# HDMI_To_MIPI_PHY.net
KiCad netlist of a schematic drawn in Altium Designer
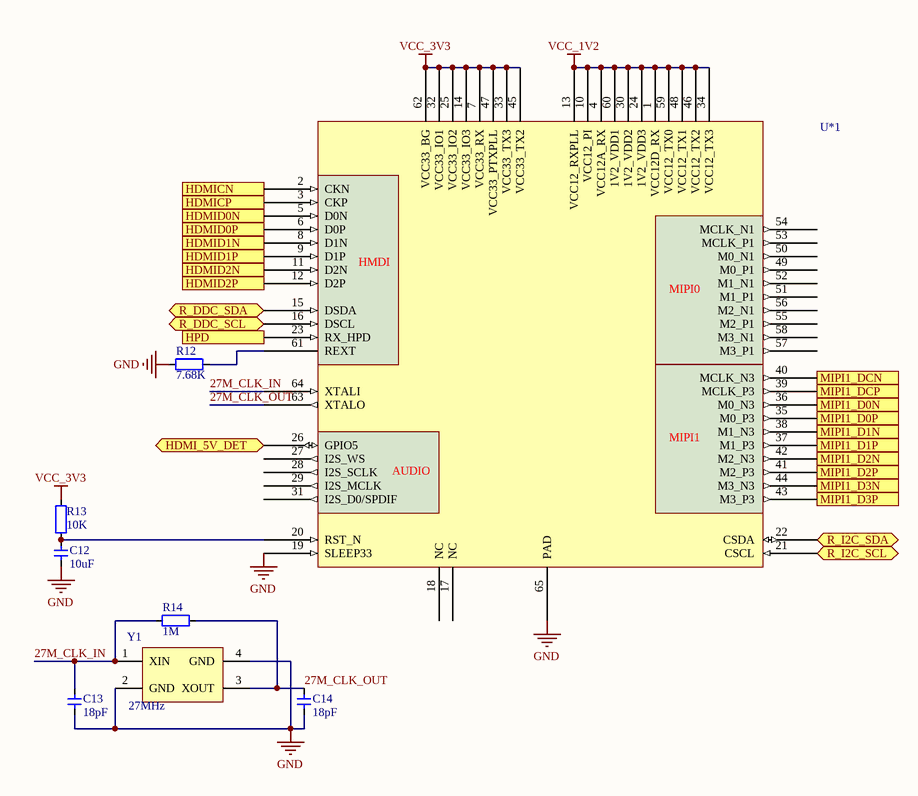
[diagram p0: HDMI_To_MIPI_PHY.SchDoc]

(export (version "E")
  (design (tool "Eeschema 10.0.6"))
  (components
    (comp (ref "C12")
      (value "10uF")
      (footprint "CAP_0402")
      (description "Capacitor")
      (libsource (lib "MyPcbLib") (part "电容-0402"))
    )
    (comp (ref "C13")
      (value "18pF")
      (footprint "CAP_0402")
      (description "Capacitor")
      (libsource (lib "MyPcbLib") (part "电容-0402"))
    )
    (comp (ref "C14")
      (value "18pF")
      (footprint "CAP_0402")
      (description "Capacitor")
      (libsource (lib "MyPcbLib") (part "电容-0402"))
    )
    (comp (ref "R12")
      (value "7.68K")
      (footprint "RES_0402")
      (description "Resistor")
      (libsource (lib "MyPcbLib") (part "电阻-0402"))
    )
    (comp (ref "R13")
      (value "10K")
      (footprint "RES_0402")
      (description "Resistor")
      (libsource (lib "") (part "电阻-0402_1"))
    )
    (comp (ref "R14")
      (value "1M")
      (footprint "RES_0402")
      (description "Resistor")
      (libsource (lib "MyPcbLib") (part "电阻-0402"))
    )
    (comp (ref "U*1")
      (value "LT6911C")
      (footprint "QFN-64-0.4mm")
      (description "HDMI to MIPI PHY")
      (libsource (lib "mLib") (part "LT6911C"))
    )
    (comp (ref "Y1")
      (value "27MHz")
      (footprint "晶振2520")
      (description "2520无源")
      (fields (field (name "MF") "ECS International") (field (name "MP") "ECS-3225S30-240-EN-TR"))
      (libsource (lib "MyPcbLib") (part "晶振-4Pin-无源"))
    )
  )
  (nets
    (net (code "1") (name "/27M_CLK_IN") (class "Default")
      (node (ref "C13") (pin "2") (pinfunction "2_2") (pintype "passive"))
      (node (ref "R14") (pin "1") (pinfunction "1_1") (pintype "passive"))
      (node (ref "U*1") (pin "64") (pinfunction "XTALI_64") (pintype "input"))
      (node (ref "Y1") (pin "1") (pinfunction "XIN_1") (pintype "passive"))
    )
    (net (code "2") (name "/27M_CLK_OUT") (class "Default")
      (node (ref "C14") (pin "2") (pinfunction "2_2") (pintype "passive"))
      (node (ref "R14") (pin "2") (pinfunction "2_2") (pintype "passive"))
      (node (ref "U*1") (pin "63") (pinfunction "XTALO_63") (pintype "output"))
      (node (ref "Y1") (pin "3") (pinfunction "XOUT_3") (pintype "passive"))
    )
    (net (code "3") (name "/HDMICN") (class "Default")
      (node (ref "U*1") (pin "2") (pinfunction "CKN_2") (pintype "input"))
    )
    (net (code "4") (name "/HDMICP") (class "Default")
      (node (ref "U*1") (pin "3") (pinfunction "CKP_3") (pintype "input"))
    )
    (net (code "5") (name "/HDMID0N") (class "Default")
      (node (ref "U*1") (pin "5") (pinfunction "D0N_5") (pintype "input"))
    )
    (net (code "6") (name "/HDMID0P") (class "Default")
      (node (ref "U*1") (pin "6") (pinfunction "D0P_6") (pintype "input"))
    )
    (net (code "7") (name "/HDMID1N") (class "Default")
      (node (ref "U*1") (pin "8") (pinfunction "D1N_8") (pintype "input"))
    )
    (net (code "8") (name "/HDMID1P") (class "Default")
      (node (ref "U*1") (pin "9") (pinfunction "D1P_9") (pintype "input"))
    )
    (net (code "9") (name "/HDMID2N") (class "Default")
      (node (ref "U*1") (pin "11") (pinfunction "D2N_11") (pintype "input"))
    )
    (net (code "10") (name "/HDMID2P") (class "Default")
      (node (ref "U*1") (pin "12") (pinfunction "D2P_12") (pintype "input"))
    )
    (net (code "11") (name "/HDMI_5V_DET") (class "Default")
      (node (ref "U*1") (pin "26") (pinfunction "GPIO5_26") (pintype "bidirectional"))
    )
    (net (code "12") (name "/HPD") (class "Default")
      (node (ref "U*1") (pin "23") (pinfunction "RX_HPD_23") (pintype "input"))
    )
    (net (code "13") (name "/MIPI1_D0N") (class "Default")
      (node (ref "U*1") (pin "36") (pinfunction "M0_N3_36") (pintype "output"))
    )
    (net (code "14") (name "/MIPI1_D0P") (class "Default")
      (node (ref "U*1") (pin "35") (pinfunction "M0_P3_35") (pintype "output"))
    )
    (net (code "15") (name "/MIPI1_D1N") (class "Default")
      (node (ref "U*1") (pin "38") (pinfunction "M1_N3_38") (pintype "output"))
    )
    (net (code "16") (name "/MIPI1_D1P") (class "Default")
      (node (ref "U*1") (pin "37") (pinfunction "M1_P3_37") (pintype "output"))
    )
    (net (code "17") (name "/MIPI1_D2N") (class "Default")
      (node (ref "U*1") (pin "42") (pinfunction "M2_N3_42") (pintype "output"))
    )
    (net (code "18") (name "/MIPI1_D2P") (class "Default")
      (node (ref "U*1") (pin "41") (pinfunction "M2_P3_41") (pintype "output"))
    )
    (net (code "19") (name "/MIPI1_D3N") (class "Default")
      (node (ref "U*1") (pin "44") (pinfunction "M3_N3_44") (pintype "output"))
    )
    (net (code "20") (name "/MIPI1_D3P") (class "Default")
      (node (ref "U*1") (pin "43") (pinfunction "M3_P3_43") (pintype "output"))
    )
    (net (code "21") (name "/MIPI1_DCN") (class "Default")
      (node (ref "U*1") (pin "40") (pinfunction "MCLK_N3_40") (pintype "output"))
    )
    (net (code "22") (name "/MIPI1_DCP") (class "Default")
      (node (ref "U*1") (pin "39") (pinfunction "MCLK_P3_39") (pintype "output"))
    )
    (net (code "23") (name "/R_DDC_SCL") (class "Default")
      (node (ref "U*1") (pin "16") (pinfunction "DSCL_16") (pintype "input"))
    )
    (net (code "24") (name "/R_DDC_SDA") (class "Default")
      (node (ref "U*1") (pin "15") (pinfunction "DSDA_15") (pintype "input"))
    )
    (net (code "25") (name "/R_I2C_SCL") (class "Default")
      (node (ref "U*1") (pin "21") (pinfunction "CSCL_21") (pintype "input"))
    )
    (net (code "26") (name "/R_I2C_SDA") (class "Default")
      (node (ref "U*1") (pin "22") (pinfunction "CSDA_22") (pintype "bidirectional"))
    )
    (net (code "27") (name "GND") (class "Default")
      (node (ref "C12") (pin "1") (pinfunction "1_1") (pintype "passive"))
      (node (ref "C13") (pin "1") (pinfunction "1_1") (pintype "passive"))
      (node (ref "C14") (pin "1") (pinfunction "1_1") (pintype "passive"))
      (node (ref "R12") (pin "1") (pinfunction "1_1") (pintype "passive"))
      (node (ref "U*1") (pin "19") (pinfunction "SLEEP33_19") (pintype "input"))
      (node (ref "U*1") (pin "65") (pinfunction "PAD_65") (pintype "power_in"))
      (node (ref "Y1") (pin "2") (pinfunction "GND_2") (pintype "passive"))
      (node (ref "Y1") (pin "4") (pinfunction "GND_4") (pintype "passive"))
    )
    (net (code "28") (name "Net-(U*1-REXT)") (class "Default")
      (node (ref "R12") (pin "2") (pinfunction "2_2") (pintype "passive"))
      (node (ref "U*1") (pin "61") (pinfunction "REXT_61") (pintype "passive"))
    )
    (net (code "29") (name "Net-(U*1-RST_N)") (class "Default")
      (node (ref "C12") (pin "2") (pinfunction "2_2") (pintype "passive"))
      (node (ref "R13") (pin "1") (pinfunction "1_1") (pintype "passive"))
      (node (ref "U*1") (pin "20") (pinfunction "RST_N_20") (pintype "input"))
    )
    (net (code "30") (name "VCC_1V2") (class "Default")
      (node (ref "U*1") (pin "1") (pinfunction "VCC12D_RX_1") (pintype "power_in"))
      (node (ref "U*1") (pin "10") (pinfunction "VCC12_PI_10") (pintype "power_in"))
      (node (ref "U*1") (pin "13") (pinfunction "VCC12_RXPLL_13") (pintype "power_in"))
      (node (ref "U*1") (pin "24") (pinfunction "1V2_VDD3_24") (pintype "power_in"))
      (node (ref "U*1") (pin "30") (pinfunction "1V2_VDD2_30") (pintype "power_in"))
      (node (ref "U*1") (pin "34") (pinfunction "VCC12_TX3_34") (pintype "power_in"))
      (node (ref "U*1") (pin "4") (pinfunction "VCC12A_RX_4") (pintype "power_in"))
      (node (ref "U*1") (pin "46") (pinfunction "VCC12_TX2_46") (pintype "power_in"))
      (node (ref "U*1") (pin "48") (pinfunction "VCC12_TX1_48") (pintype "power_in"))
      (node (ref "U*1") (pin "59") (pinfunction "VCC12_TX0_59") (pintype "power_in"))
      (node (ref "U*1") (pin "60") (pinfunction "1V2_VDD1_60") (pintype "power_in"))
    )
    (net (code "31") (name "VCC_3V3") (class "Default")
      (node (ref "R13") (pin "2") (pinfunction "2_2") (pintype "passive"))
      (node (ref "U*1") (pin "14") (pinfunction "VCC33_IO3_14") (pintype "power_in"))
      (node (ref "U*1") (pin "25") (pinfunction "VCC33_IO2_25") (pintype "power_in"))
      (node (ref "U*1") (pin "32") (pinfunction "VCC33_IO1_32") (pintype "power_in"))
      (node (ref "U*1") (pin "33") (pinfunction "VCC33_TX3_33") (pintype "power_in"))
      (node (ref "U*1") (pin "45") (pinfunction "VCC33_TX2_45") (pintype "power_in"))
      (node (ref "U*1") (pin "47") (pinfunction "VCC33_PTXPLL_47") (pintype "power_in"))
      (node (ref "U*1") (pin "62") (pinfunction "VCC33_BG_62") (pintype "power_in"))
      (node (ref "U*1") (pin "7") (pinfunction "VCC33_RX_7") (pintype "power_in"))
    )
    (net (code "32") (name "unconnected-(U*1-I2S_D0{slash}SPDIF-Pad31)") (class "Default")
      (node (ref "U*1") (pin "31") (pinfunction "I2S_D0/SPDIF_31") (pintype "output"))
    )
    (net (code "33") (name "unconnected-(U*1-I2S_MCLK-Pad29)") (class "Default")
      (node (ref "U*1") (pin "29") (pinfunction "I2S_MCLK_29") (pintype "output"))
    )
    (net (code "34") (name "unconnected-(U*1-I2S_SCLK-Pad28)") (class "Default")
      (node (ref "U*1") (pin "28") (pinfunction "I2S_SCLK_28") (pintype "output"))
    )
    (net (code "35") (name "unconnected-(U*1-I2S_WS-Pad27)") (class "Default")
      (node (ref "U*1") (pin "27") (pinfunction "I2S_WS_27") (pintype "output"))
    )
    (net (code "36") (name "unconnected-(U*1-M0_N1-Pad50)") (class "Default")
      (node (ref "U*1") (pin "50") (pinfunction "M0_N1_50") (pintype "output"))
    )
    (net (code "37") (name "unconnected-(U*1-M0_P1-Pad49)") (class "Default")
      (node (ref "U*1") (pin "49") (pinfunction "M0_P1_49") (pintype "output"))
    )
    (net (code "38") (name "unconnected-(U*1-M1_N1-Pad52)") (class "Default")
      (node (ref "U*1") (pin "52") (pinfunction "M1_N1_52") (pintype "output"))
    )
    (net (code "39") (name "unconnected-(U*1-M1_P1-Pad51)") (class "Default")
      (node (ref "U*1") (pin "51") (pinfunction "M1_P1_51") (pintype "output"))
    )
    (net (code "40") (name "unconnected-(U*1-M2_N1-Pad56)") (class "Default")
      (node (ref "U*1") (pin "56") (pinfunction "M2_N1_56") (pintype "output"))
    )
    (net (code "41") (name "unconnected-(U*1-M2_P1-Pad55)") (class "Default")
      (node (ref "U*1") (pin "55") (pinfunction "M2_P1_55") (pintype "output"))
    )
    (net (code "42") (name "unconnected-(U*1-M3_N1-Pad58)") (class "Default")
      (node (ref "U*1") (pin "58") (pinfunction "M3_N1_58") (pintype "output"))
    )
    (net (code "43") (name "unconnected-(U*1-M3_P1-Pad57)") (class "Default")
      (node (ref "U*1") (pin "57") (pinfunction "M3_P1_57") (pintype "output"))
    )
    (net (code "44") (name "unconnected-(U*1-MCLK_N1-Pad54)") (class "Default")
      (node (ref "U*1") (pin "54") (pinfunction "MCLK_N1_54") (pintype "output"))
    )
    (net (code "45") (name "unconnected-(U*1-MCLK_P1-Pad53)") (class "Default")
      (node (ref "U*1") (pin "53") (pinfunction "MCLK_P1_53") (pintype "output"))
    )
    (net (code "46") (name "unconnected-(U*1-NC-Pad17)") (class "Default")
      (node (ref "U*1") (pin "17") (pinfunction "NC_17") (pintype "tri_state"))
    )
    (net (code "47") (name "unconnected-(U*1-NC-Pad18)") (class "Default")
      (node (ref "U*1") (pin "18") (pinfunction "NC_18") (pintype "tri_state"))
    )
  )
)
